# BSheetSchematicTemplateWWU.net
KiCad netlist of a schematic drawn in Altium Designer
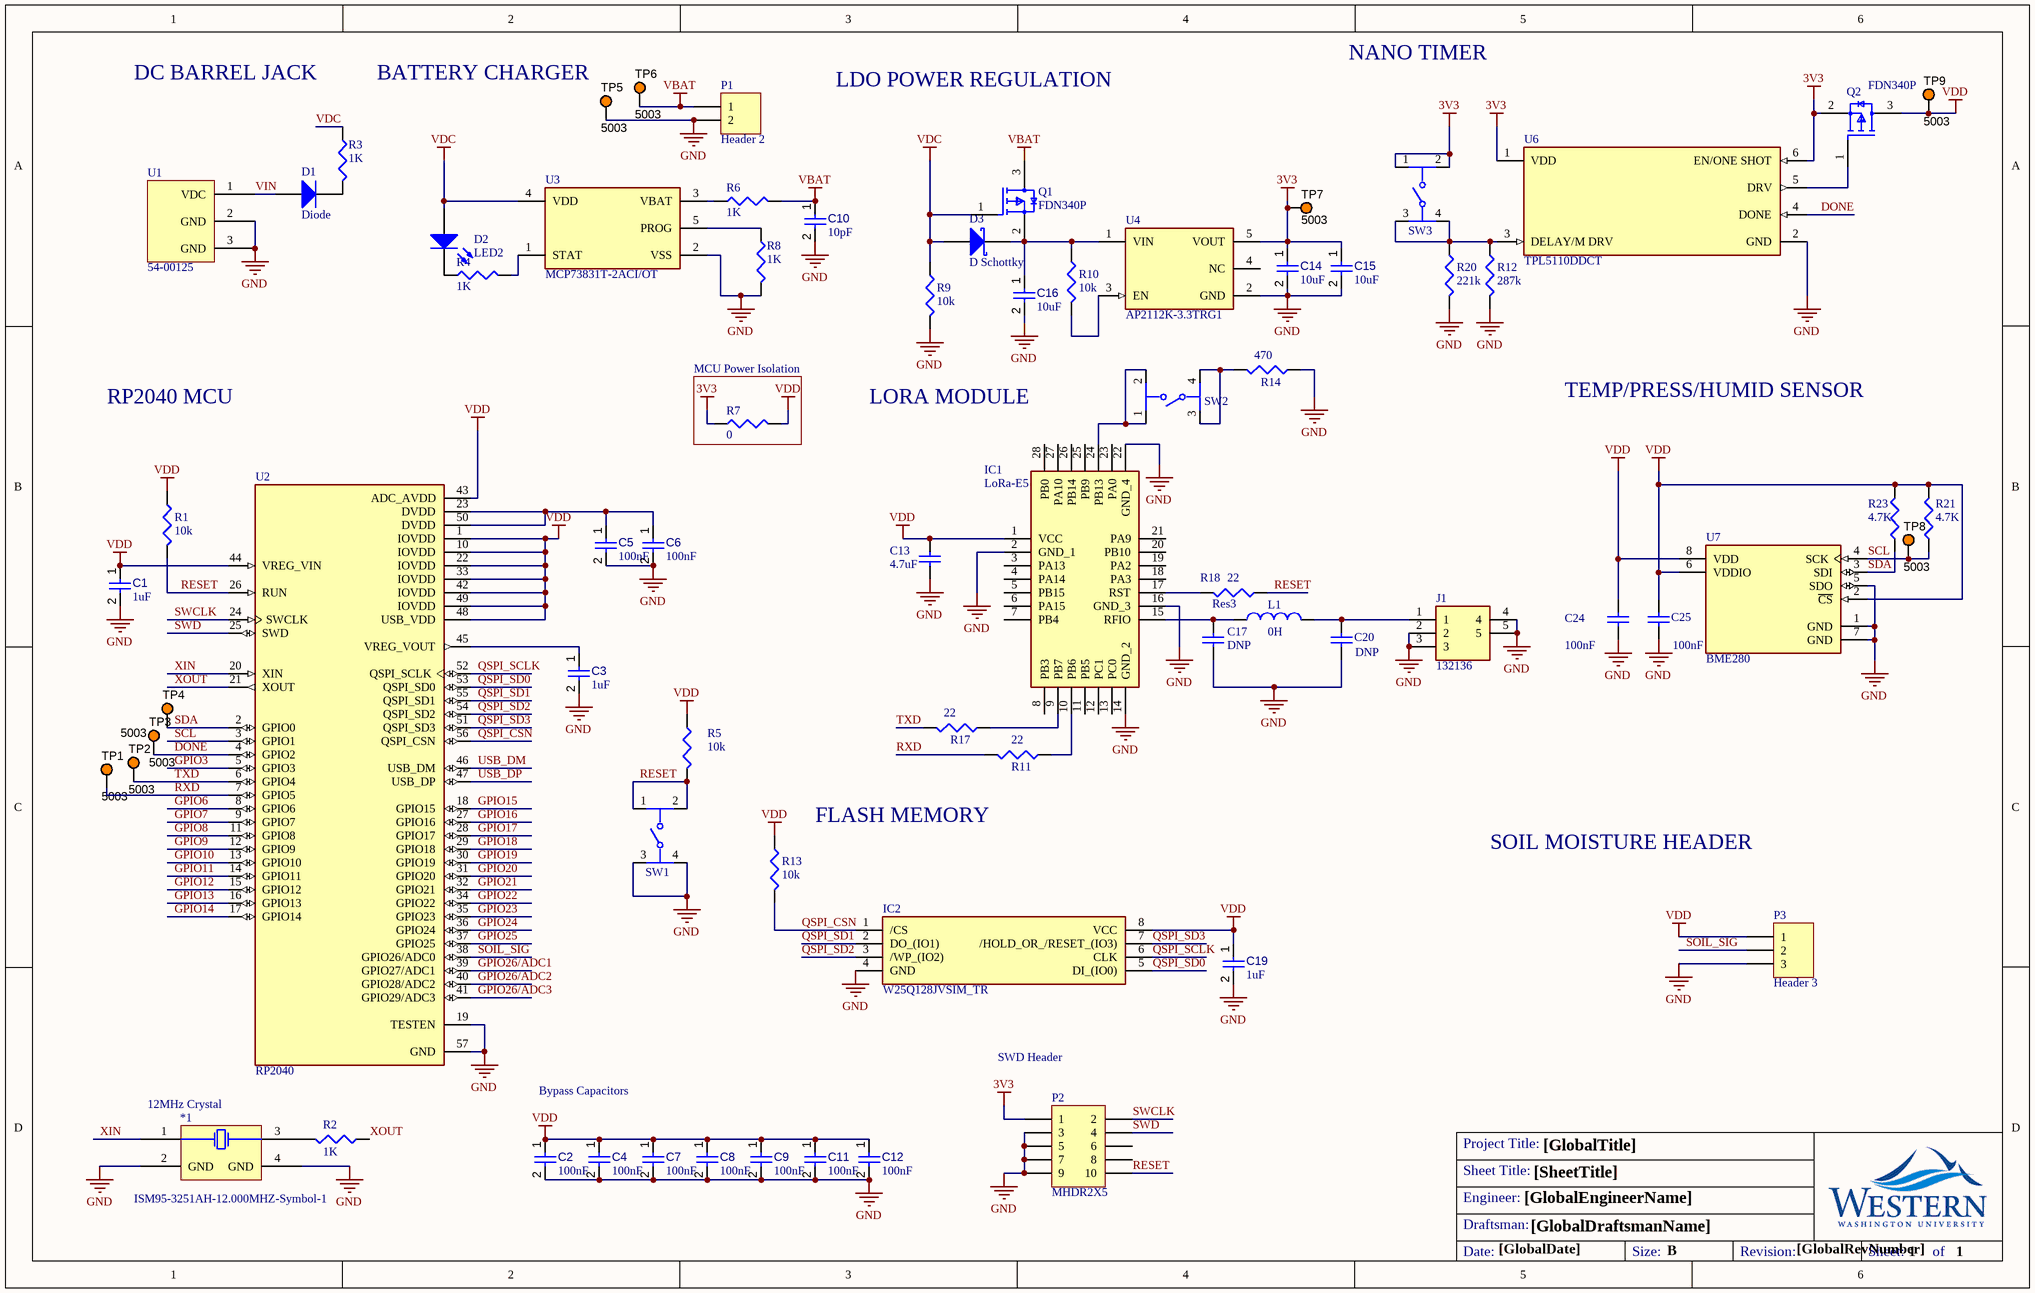
[diagram p0: BSheetSchematicTemplateWWU.SchDoc]

(export (version "E")
  (design (tool "Eeschema 10.0.6"))
  (components
    (comp (ref "*1")
      (value "ISM95-3251AH-12.000MHZ-Symbol-1")
      (footprint "OSC_ISM951251AH32000MHZ")
      (libsource (lib "SeniorProject") (part "ISM95-3251AH-12.000MHZ-Symbol-1"))
    )
    (comp (ref "C1")
      (value "1uF")
      (footprint "CAPC1608X87X35NL15T15")
      (description "Chip Capacitor, 10 pF, +/- 0.25 pF, 50 V, 0603 (1608 Metric)")
      (fields
        (field (name "TOLERANCE") "0.25%")
        (field (name "Comment") "Capacitor 10 pF +/- 0.25 pF 50 V 0603")
      )
      (libsource (lib "Western Washington University") (part "CAP-NP-2"))
    )
    (comp (ref "C2")
      (value "100nF")
      (footprint "CAPC1608X87X35NL15T15")
      (description "Chip Capacitor, 10 pF, +/- 0.25 pF, 50 V, 0603 (1608 Metric)")
      (fields
        (field (name "TOLERANCE") "0.25%")
        (field (name "Comment") "Capacitor 10 pF +/- 0.25 pF 50 V 0603")
      )
      (libsource (lib "Western Washington University") (part "CAP-NP-2"))
    )
    (comp (ref "C3")
      (value "1uF")
      (footprint "CAPC1608X87X35NL15T15")
      (description "Chip Capacitor, 10 pF, +/- 0.25 pF, 50 V, 0603 (1608 Metric)")
      (fields
        (field (name "TOLERANCE") "0.25%")
        (field (name "Comment") "Capacitor 10 pF +/- 0.25 pF 50 V 0603")
      )
      (libsource (lib "Western Washington University") (part "CAP-NP-2"))
    )
    (comp (ref "C4")
      (value "100nF")
      (footprint "CAPC1608X87X35NL15T15")
      (description "Chip Capacitor, 10 pF, +/- 0.25 pF, 50 V, 0603 (1608 Metric)")
      (fields
        (field (name "TOLERANCE") "0.25%")
        (field (name "Comment") "Capacitor 10 pF +/- 0.25 pF 50 V 0603")
      )
      (libsource (lib "Western Washington University") (part "CAP-NP-2"))
    )
    (comp (ref "C5")
      (value "100nF")
      (footprint "CAPC1608X87X35NL15T15")
      (description "Chip Capacitor, 10 pF, +/- 0.25 pF, 50 V, 0603 (1608 Metric)")
      (fields
        (field (name "TOLERANCE") "0.25%")
        (field (name "Comment") "Capacitor 10 pF +/- 0.25 pF 50 V 0603")
      )
      (libsource (lib "Western Washington University") (part "CAP-NP-2"))
    )
    (comp (ref "C6")
      (value "100nF")
      (footprint "CAPC1608X87X35NL15T15")
      (description "Chip Capacitor, 10 pF, +/- 0.25 pF, 50 V, 0603 (1608 Metric)")
      (fields
        (field (name "TOLERANCE") "0.25%")
        (field (name "Comment") "Capacitor 10 pF +/- 0.25 pF 50 V 0603")
      )
      (libsource (lib "Western Washington University") (part "CAP-NP-2"))
    )
    (comp (ref "C7")
      (value "100nF")
      (footprint "CAPC1608X87X35NL15T15")
      (description "Chip Capacitor, 10 pF, +/- 0.25 pF, 50 V, 0603 (1608 Metric)")
      (fields
        (field (name "TOLERANCE") "0.25%")
        (field (name "Comment") "Capacitor 10 pF +/- 0.25 pF 50 V 0603")
      )
      (libsource (lib "Western Washington University") (part "CAP-NP-2"))
    )
    (comp (ref "C8")
      (value "100nF")
      (footprint "CAPC1608X87X35NL15T15")
      (description "Chip Capacitor, 10 pF, +/- 0.25 pF, 50 V, 0603 (1608 Metric)")
      (fields
        (field (name "TOLERANCE") "0.25%")
        (field (name "Comment") "Capacitor 10 pF +/- 0.25 pF 50 V 0603")
      )
      (libsource (lib "Western Washington University") (part "CAP-NP-2"))
    )
    (comp (ref "C9")
      (value "100nF")
      (footprint "CAPC1608X87X35NL15T15")
      (description "Chip Capacitor, 10 pF, +/- 0.25 pF, 50 V, 0603 (1608 Metric)")
      (fields
        (field (name "TOLERANCE") "0.25%")
        (field (name "Comment") "Capacitor 10 pF +/- 0.25 pF 50 V 0603")
      )
      (libsource (lib "Western Washington University") (part "CAP-NP-2"))
    )
    (comp (ref "C10")
      (value "10pF")
      (footprint "CAPC1608X87X35NL15T15")
      (description "Chip Capacitor, 10 pF, +/- 0.25 pF, 50 V, 0603 (1608 Metric)")
      (fields
        (field (name "TOLERANCE") "0.25%")
        (field (name "Comment") "Capacitor 10 pF +/- 0.25 pF 50 V 0603")
      )
      (libsource (lib "Western Washington University") (part "CAP-NP-2"))
    )
    (comp (ref "C11")
      (value "100nF")
      (footprint "CAPC1608X87X35NL15T15")
      (description "Chip Capacitor, 10 pF, +/- 0.25 pF, 50 V, 0603 (1608 Metric)")
      (fields
        (field (name "TOLERANCE") "0.25%")
        (field (name "Comment") "Capacitor 10 pF +/- 0.25 pF 50 V 0603")
      )
      (libsource (lib "Western Washington University") (part "CAP-NP-2"))
    )
    (comp (ref "C12")
      (value "100nF")
      (footprint "CAPC1608X87X35NL15T15")
      (description "Chip Capacitor, 10 pF, +/- 0.25 pF, 50 V, 0603 (1608 Metric)")
      (fields
        (field (name "TOLERANCE") "0.25%")
        (field (name "Comment") "Capacitor 10 pF +/- 0.25 pF 50 V 0603")
      )
      (libsource (lib "Western Washington University") (part "CAP-NP-2"))
    )
    (comp (ref "C13")
      (value "4.7uF")
      (footprint "1608[0603]")
      (description "Capacitor (Semiconductor SIM Model)")
      (fields (field (name "Comment") "Cap Semi") (field (name "PUBLISHER") "Altium Limited"))
      (libsource (lib "Miscellaneous Devices") (part "Cap Semi"))
    )
    (comp (ref "C14")
      (value "10uF")
      (footprint "CAPC1608X87X35NL15T15")
      (description "Chip Capacitor, 10 pF, +/- 0.25 pF, 50 V, 0603 (1608 Metric)")
      (fields
        (field (name "TOLERANCE") "0.25%")
        (field (name "Comment") "Capacitor 10 pF +/- 0.25 pF 50 V 0603")
      )
      (libsource (lib "Western Washington University") (part "CAP-NP-2"))
    )
    (comp (ref "C15")
      (value "10uF")
      (footprint "CAPC1608X87X35NL15T15")
      (description "Chip Capacitor, 10 pF, +/- 0.25 pF, 50 V, 0603 (1608 Metric)")
      (fields
        (field (name "TOLERANCE") "0.25%")
        (field (name "Comment") "Capacitor 10 pF +/- 0.25 pF 50 V 0603")
      )
      (libsource (lib "Western Washington University") (part "CAP-NP-2"))
    )
    (comp (ref "C16")
      (value "10uF")
      (footprint "CAPC1608X87X35NL15T15")
      (description "Chip Capacitor, 10 pF, +/- 0.25 pF, 50 V, 0603 (1608 Metric)")
      (fields
        (field (name "TOLERANCE") "0.25%")
        (field (name "Comment") "Capacitor 10 pF +/- 0.25 pF 50 V 0603")
      )
      (libsource (lib "Western Washington University") (part "CAP-NP-2"))
    )
    (comp (ref "C17")
      (value "DNP")
      (footprint "1608[0603]")
      (description "Capacitor (Semiconductor SIM Model)")
      (fields (field (name "Comment") "Cap Semi") (field (name "PUBLISHER") "Altium Limited"))
      (libsource (lib "Miscellaneous Devices") (part "Cap Semi"))
    )
    (comp (ref "C19")
      (value "1uF")
      (footprint "CAPC1608X87X35NL15T15")
      (description "Chip Capacitor, 10 pF, +/- 0.25 pF, 50 V, 0603 (1608 Metric)")
      (fields
        (field (name "TOLERANCE") "0.25%")
        (field (name "Comment") "Capacitor 10 pF +/- 0.25 pF 50 V 0603")
      )
      (libsource (lib "Western Washington University") (part "CAP-NP-2"))
    )
    (comp (ref "C20")
      (value "DNP")
      (footprint "1608[0603]")
      (description "Capacitor (Semiconductor SIM Model)")
      (fields (field (name "Comment") "Cap Semi") (field (name "PUBLISHER") "Altium Limited"))
      (libsource (lib "Miscellaneous Devices") (part "Cap Semi"))
    )
    (comp (ref "C24")
      (value "100nF")
      (footprint "1608[0603]")
      (description "Capacitor (Semiconductor SIM Model)")
      (fields (field (name "Comment") "Cap Semi") (field (name "PUBLISHER") "Altium Limited"))
      (libsource (lib "Miscellaneous Devices") (part "Cap Semi"))
    )
    (comp (ref "C25")
      (value "100nF")
      (footprint "1608[0603]")
      (description "Capacitor (Semiconductor SIM Model)")
      (fields (field (name "Comment") "Cap Semi") (field (name "PUBLISHER") "Altium Limited"))
      (libsource (lib "Miscellaneous Devices") (part "Cap Semi"))
    )
    (comp (ref "D1")
      (value "Diode")
      (footprint "SMC")
      (description "Default Diode")
      (fields (field (name "PUBLISHER") "Altium Limited"))
      (libsource (lib "Miscellaneous Devices") (part "Diode"))
    )
    (comp (ref "D2")
      (value "LED2")
      (footprint "3.2X1.6X1.1")
      (description "Typical RED, GREEN, YELLOW, AMBER GaAs LED")
      (fields (field (name "PUBLISHER") "Altium Limited"))
      (libsource (lib "Miscellaneous Devices") (part "LED2"))
    )
    (comp (ref "D3")
      (value "D Schottky")
      (footprint "SMB")
      (description "Schottky Diode")
      (fields (field (name "PUBLISHER") "Altium Limited"))
      (libsource (lib "Miscellaneous Devices") (part "D Schottky"))
    )
    (comp (ref "IC1")
      (value "LoRa-E5")
      (footprint "SamacSys:LoRaE5")
      (description "Integrated Circuit")
      (libsource (lib "*") (part "LoRa-E5"))
    )
    (comp (ref "IC2")
      (value "W25Q128JVSIM_TR")
      (footprint "SOIC127P790X216-8N")
      (description "Integrated Circuit")
      (fields
        (field (name "MANUFACTURER_PART_NUMBER") "W25Q128JVSIM TR")
        (field (name "MOUSER PART NUMBER") "454-W25Q128JVSIMTR")
      )
      (libsource (lib "*") (part "W25Q128JVSIM_TR"))
    )
    (comp (ref "J1")
      (value "132136")
      (footprint "132136")
      (description "Connector")
      (fields (field (name "MOUSER PART NUMBER") "523-132136"))
      (libsource (lib "*") (part "132136"))
    )
    (comp (ref "L1")
      (value "0H")
      (footprint "0603")
      (description "Inductor")
      (fields (field (name "PUBLISHER") "Altium Limited"))
      (libsource (lib "Miscellaneous Devices") (part "Inductor"))
    )
    (comp (ref "P1")
      (value "Header 2")
      (footprint "HDR1X2")
      (description "Header, 2-Pin")
      (fields (field (name "PUBLISHER") "Altium Limited"))
      (libsource (lib "Miscellaneous Connectors") (part "Header 2"))
    )
    (comp (ref "P2")
      (value "MHDR2X5")
      (footprint "MHDR2X5")
      (description "Header, 5-Pin, Dual row")
      (fields (field (name "PUBLISHER") "Altium Limited"))
      (libsource (lib "Miscellaneous Connectors") (part "MHDR2X5"))
    )
    (comp (ref "P3")
      (value "Header 3")
      (footprint "HDR1X3")
      (description "Header, 3-Pin")
      (fields (field (name "PUBLISHER") "Altium Limited"))
      (libsource (lib "Miscellaneous Connectors") (part "Header 3"))
    )
    (comp (ref "Q1")
      (value "FDN340P")
      (footprint "FP-527AG-MFG")
      (description "MOSFET P-CH 20V 2A SSOT3")
      (libsource (lib "Altium Content Vault") (part "d23f43cc42f60b967b7caccf14518fd"))
    )
    (comp (ref "Q2")
      (value "FDN340P")
      (footprint "FP-527AG-MFG")
      (description "MOSFET P-CH 20V 2A SSOT3")
      (libsource (lib "Altium Content Vault") (part "d23f43cc42f60b967b7caccf14518fd"))
    )
    (comp (ref "R1")
      (value "10k")
      (footprint "J1-0603")
      (description "Resistor")
      (fields (field (name "Comment") "Res3") (field (name "PUBLISHER") "Altium Limited"))
      (libsource (lib "Miscellaneous Devices") (part "Res3"))
    )
    (comp (ref "R2")
      (value "1K")
      (footprint "J1-0603")
      (description "Resistor")
      (fields (field (name "Comment") "Res3") (field (name "PUBLISHER") "Altium Limited"))
      (libsource (lib "Miscellaneous Devices") (part "Res3"))
    )
    (comp (ref "R3")
      (value "1K")
      (footprint "J1-0603")
      (description "Resistor")
      (fields (field (name "Comment") "Res3") (field (name "PUBLISHER") "Altium Limited"))
      (libsource (lib "Miscellaneous Devices") (part "Res3"))
    )
    (comp (ref "R4")
      (value "1K")
      (footprint "J1-0603")
      (description "Resistor")
      (fields (field (name "Comment") "Res3") (field (name "PUBLISHER") "Altium Limited"))
      (libsource (lib "Miscellaneous Devices") (part "Res3"))
    )
    (comp (ref "R5")
      (value "10k")
      (footprint "J1-0603")
      (description "Resistor")
      (fields (field (name "Comment") "Res3") (field (name "PUBLISHER") "Altium Limited"))
      (libsource (lib "Miscellaneous Devices") (part "Res3"))
    )
    (comp (ref "R6")
      (value "1K")
      (footprint "J1-0603")
      (description "Resistor")
      (fields (field (name "Comment") "Res3") (field (name "PUBLISHER") "Altium Limited"))
      (libsource (lib "Miscellaneous Devices") (part "Res3"))
    )
    (comp (ref "R7")
      (value "0")
      (footprint "J1-0603")
      (description "Resistor")
      (fields (field (name "Comment") "Res3") (field (name "PUBLISHER") "Altium Limited"))
      (libsource (lib "Miscellaneous Devices") (part "Res3"))
    )
    (comp (ref "R8")
      (value "1K")
      (footprint "J1-0603")
      (description "Resistor")
      (fields (field (name "Comment") "Res3") (field (name "PUBLISHER") "Altium Limited"))
      (libsource (lib "Miscellaneous Devices") (part "Res3"))
    )
    (comp (ref "R9")
      (value "10k")
      (footprint "J1-0603")
      (description "Resistor")
      (fields (field (name "Comment") "Res3") (field (name "PUBLISHER") "Altium Limited"))
      (libsource (lib "Miscellaneous Devices") (part "Res3"))
    )
    (comp (ref "R10")
      (value "10k")
      (footprint "J1-0603")
      (description "Resistor")
      (fields (field (name "Comment") "Res3") (field (name "PUBLISHER") "Altium Limited"))
      (libsource (lib "Miscellaneous Devices") (part "Res3"))
    )
    (comp (ref "R11")
      (value "22")
      (footprint "J1-0603")
      (description "Resistor")
      (fields (field (name "Comment") "Res3") (field (name "PUBLISHER") "Altium Limited"))
      (libsource (lib "Miscellaneous Devices") (part "Res3"))
    )
    (comp (ref "R12")
      (value "287k")
      (footprint "J1-0603")
      (description "Resistor")
      (fields (field (name "Comment") "Res3") (field (name "PUBLISHER") "Altium Limited"))
      (libsource (lib "Miscellaneous Devices") (part "Res3"))
    )
    (comp (ref "R13")
      (value "10k")
      (footprint "J1-0603")
      (description "Resistor")
      (fields (field (name "Comment") "Res3") (field (name "PUBLISHER") "Altium Limited"))
      (libsource (lib "Miscellaneous Devices") (part "Res3"))
    )
    (comp (ref "R14")
      (value "470")
      (footprint "J1-0603")
      (description "Resistor")
      (fields (field (name "Comment") "Res3") (field (name "PUBLISHER") "Altium Limited"))
      (libsource (lib "Miscellaneous Devices") (part "Res3"))
    )
    (comp (ref "R17")
      (value "22")
      (footprint "J1-0603")
      (description "Resistor")
      (fields (field (name "Comment") "Res3") (field (name "PUBLISHER") "Altium Limited"))
      (libsource (lib "Miscellaneous Devices") (part "Res3"))
    )
    (comp (ref "R18")
      (value "Res3")
      (footprint "J1-0603")
      (description "Resistor")
      (fields (field (name "ALTIUM_VALUE") "22") (field (name "PUBLISHER") "Altium Limited"))
      (libsource (lib "Miscellaneous Devices") (part "Res3"))
    )
    (comp (ref "R20")
      (value "221k")
      (footprint "J1-0603")
      (description "Resistor")
      (fields (field (name "Comment") "Res3") (field (name "PUBLISHER") "Altium Limited"))
      (libsource (lib "Miscellaneous Devices") (part "Res3"))
    )
    (comp (ref "R21")
      (value "4.7K")
      (footprint "J1-0603")
      (description "Resistor")
      (fields (field (name "Comment") "Res3") (field (name "PUBLISHER") "Altium Limited"))
      (libsource (lib "Miscellaneous Devices") (part "Res3"))
    )
    (comp (ref "R23")
      (value "4.7K")
      (footprint "J1-0603")
      (description "Resistor")
      (fields (field (name "Comment") "Res3") (field (name "PUBLISHER") "Altium Limited"))
      (libsource (lib "Miscellaneous Devices") (part "Res3"))
    )
    (comp (ref "SW1")
      (value "PTS645SM43SMTR92LFS")
      (footprint "FP-PTS645SM43SMTR92LFS-MFG")
      (description "SWITCH TACTILE SPST-NO 0.05A 12V")
      (libsource (lib "Altium Content Vault") (part "1adf0dd01260c80cf25a44bfd6b99ba"))
    )
    (comp (ref "SW2")
      (value "PTS645SM43SMTR92LFS")
      (footprint "FP-PTS645SM43SMTR92LFS-MFG")
      (description "SWITCH TACTILE SPST-NO 0.05A 12V")
      (libsource (lib "Altium Content Vault") (part "1adf0dd01260c80cf25a44bfd6b99ba"))
    )
    (comp (ref "SW3")
      (value "PTS645SM43SMTR92LFS")
      (footprint "FP-PTS645SM43SMTR92LFS-MFG")
      (description "SWITCH TACTILE SPST-NO 0.05A 12V")
      (libsource (lib "Altium Content Vault") (part "1adf0dd01260c80cf25a44bfd6b99ba"))
    )
    (comp (ref "TP1")
      (value "5003")
      (footprint "KSTN-5003")
      (description "Test Point, Orange, Height 4.6 mm, Tail Length 3 mm, 1-Pin THD, RoHS")
      (fields (field (name "MANUFACTURER") "Keystone"))
      (libsource (lib "Western Washington University") (part "TESTPOINT_ORANGE"))
    )
    (comp (ref "TP2")
      (value "5003")
      (footprint "KSTN-5003")
      (description "Test Point, Orange, Height 4.6 mm, Tail Length 3 mm, 1-Pin THD, RoHS")
      (fields (field (name "MANUFACTURER") "Keystone"))
      (libsource (lib "Western Washington University") (part "TESTPOINT_ORANGE"))
    )
    (comp (ref "TP3")
      (value "5003")
      (footprint "KSTN-5003")
      (description "Test Point, Orange, Height 4.6 mm, Tail Length 3 mm, 1-Pin THD, RoHS")
      (fields (field (name "MANUFACTURER") "Keystone"))
      (libsource (lib "Western Washington University") (part "TESTPOINT_ORANGE"))
    )
    (comp (ref "TP4")
      (value "5003")
      (footprint "KSTN-5003")
      (description "Test Point, Orange, Height 4.6 mm, Tail Length 3 mm, 1-Pin THD, RoHS")
      (fields (field (name "MANUFACTURER") "Keystone"))
      (libsource (lib "Western Washington University") (part "TESTPOINT_ORANGE"))
    )
    (comp (ref "TP5")
      (value "5003")
      (footprint "KSTN-5003")
      (description "Test Point, Orange, Height 4.6 mm, Tail Length 3 mm, 1-Pin THD, RoHS")
      (fields (field (name "MANUFACTURER") "Keystone"))
      (libsource (lib "Western Washington University") (part "TESTPOINT_ORANGE"))
    )
    (comp (ref "TP6")
      (value "5003")
      (footprint "KSTN-5003")
      (description "Test Point, Orange, Height 4.6 mm, Tail Length 3 mm, 1-Pin THD, RoHS")
      (fields (field (name "MANUFACTURER") "Keystone"))
      (libsource (lib "Western Washington University") (part "TESTPOINT_ORANGE"))
    )
    (comp (ref "TP7")
      (value "5003")
      (footprint "KSTN-5003")
      (description "Test Point, Orange, Height 4.6 mm, Tail Length 3 mm, 1-Pin THD, RoHS")
      (fields (field (name "MANUFACTURER") "Keystone"))
      (libsource (lib "Western Washington University") (part "TESTPOINT_ORANGE"))
    )
    (comp (ref "TP8")
      (value "5003")
      (footprint "KSTN-5003")
      (description "Test Point, Orange, Height 4.6 mm, Tail Length 3 mm, 1-Pin THD, RoHS")
      (fields (field (name "MANUFACTURER") "Keystone"))
      (libsource (lib "Western Washington University") (part "TESTPOINT_ORANGE"))
    )
    (comp (ref "TP9")
      (value "5003")
      (footprint "KSTN-5003")
      (description "Test Point, Orange, Height 4.6 mm, Tail Length 3 mm, 1-Pin THD, RoHS")
      (fields (field (name "MANUFACTURER") "Keystone"))
      (libsource (lib "Western Washington University") (part "TESTPOINT_ORANGE"))
    )
    (comp (ref "U1")
      (value "54-00125")
      (footprint "54-00125")
      (description "3.5x1.1mm Barrel Jack Connector")
      (libsource (lib "SeniorProject") (part "54-00125"))
    )
    (comp (ref "U2")
      (value "RP2040")
      (footprint "QFN40P700X700X90-57N-D")
      (description "RP2040 Raspberry Pi Pico - ARMÂ® CortexÂ®-M0+ MCU 32-Bit Embedded Evaluation Board")
      (fields (field (name "MF") "Raspberry Pi"))
      (libsource (lib "RP2040") (part "RP2040"))
    )
    (comp (ref "U3")
      (value "MCP73831T-2ACI/OT")
      (footprint "FP-C04-091-OT-IPC_B")
      (description "IC CONTROLLR LI-ION 4.2V SOT23-5")
      (libsource (lib "Altium Content Vault") (part "61f5a3bb3429d9e0caadea342aa3b19"))
    )
    (comp (ref "U4")
      (value "AP2112K-3.3TRG1")
      (footprint "FP-SOT25-IPC_A")
      (description "IC REG LINEAR 3.3V 600MA SOT25")
      (libsource (lib "Altium Content Vault") (part "c8ab751aee5229183125ab046a11caa"))
    )
    (comp (ref "U6")
      (value "TPL5110DDCT")
      (footprint "FP-DDC0006A-MFG")
      (description "IC OSC PROG TIMER TSOT23-6")
      (fields
        (field (name "OCTOPART") "https://octopart.com/tpl5110ddct-texas+instruments-52670271")
        (field (name "MANUFACTURER") "Texas Instruments")
      )
      (libsource (lib "Altium Content Vault") (part "6ed543a5282c23458c04814cca5b1ac"))
    )
    (comp (ref "U7")
      (value "BME280")
      (footprint "FP-BME280-MFG")
      (description "SENSOR PRESSURE HUMIDITY TEMP")
      (libsource (lib "Altium Content Vault") (part "d58e2f6669bc67e6a2bc6a28610ca79"))
    )
  )
  (nets
    (net (code "1") (name "/DONE") (class "Default")
      (node (ref "TP3") (pin "1") (pinfunction "1_1") (pintype "passive"))
      (node (ref "U2") (pin "4") (pinfunction "GPIO2_4") (pintype "bidirectional"))
      (node (ref "U6") (pin "4") (pinfunction "DONE_4") (pintype "input"))
    )
    (net (code "2") (name "/GPIO3") (class "Default")
      (node (ref "U2") (pin "5") (pinfunction "GPIO3_5") (pintype "bidirectional"))
    )
    (net (code "3") (name "/GPIO6") (class "Default")
      (node (ref "U2") (pin "8") (pinfunction "GPIO6_8") (pintype "bidirectional"))
    )
    (net (code "4") (name "/GPIO7") (class "Default")
      (node (ref "U2") (pin "9") (pinfunction "GPIO7_9") (pintype "bidirectional"))
    )
    (net (code "5") (name "/GPIO8") (class "Default")
      (node (ref "U2") (pin "11") (pinfunction "GPIO8_11") (pintype "bidirectional"))
    )
    (net (code "6") (name "/GPIO9") (class "Default")
      (node (ref "U2") (pin "12") (pinfunction "GPIO9_12") (pintype "bidirectional"))
    )
    (net (code "7") (name "/GPIO10") (class "Default")
      (node (ref "U2") (pin "13") (pinfunction "GPIO10_13") (pintype "bidirectional"))
    )
    (net (code "8") (name "/GPIO11") (class "Default")
      (node (ref "U2") (pin "14") (pinfunction "GPIO11_14") (pintype "bidirectional"))
    )
    (net (code "9") (name "/GPIO12") (class "Default")
      (node (ref "U2") (pin "15") (pinfunction "GPIO12_15") (pintype "bidirectional"))
    )
    (net (code "10") (name "/GPIO13") (class "Default")
      (node (ref "U2") (pin "16") (pinfunction "GPIO13_16") (pintype "bidirectional"))
    )
    (net (code "11") (name "/GPIO14") (class "Default")
      (node (ref "U2") (pin "17") (pinfunction "GPIO14_17") (pintype "bidirectional"))
    )
    (net (code "12") (name "/GPIO15") (class "Default")
      (node (ref "U2") (pin "18") (pinfunction "GPIO15_18") (pintype "bidirectional"))
    )
    (net (code "13") (name "/GPIO16") (class "Default")
      (node (ref "U2") (pin "27") (pinfunction "GPIO16_27") (pintype "bidirectional"))
    )
    (net (code "14") (name "/GPIO17") (class "Default")
      (node (ref "U2") (pin "28") (pinfunction "GPIO17_28") (pintype "bidirectional"))
    )
    (net (code "15") (name "/GPIO18") (class "Default")
      (node (ref "U2") (pin "29") (pinfunction "GPIO18_29") (pintype "bidirectional"))
    )
    (net (code "16") (name "/GPIO19") (class "Default")
      (node (ref "U2") (pin "30") (pinfunction "GPIO19_30") (pintype "bidirectional"))
    )
    (net (code "17") (name "/GPIO20") (class "Default")
      (node (ref "U2") (pin "31") (pinfunction "GPIO20_31") (pintype "bidirectional"))
    )
    (net (code "18") (name "/GPIO21") (class "Default")
      (node (ref "U2") (pin "32") (pinfunction "GPIO21_32") (pintype "bidirectional"))
    )
    (net (code "19") (name "/GPIO22") (class "Default")
      (node (ref "U2") (pin "34") (pinfunction "GPIO22_34") (pintype "bidirectional"))
    )
    (net (code "20") (name "/GPIO23") (class "Default")
      (node (ref "U2") (pin "35") (pinfunction "GPIO23_35") (pintype "bidirectional"))
    )
    (net (code "21") (name "/GPIO24") (class "Default")
      (node (ref "U2") (pin "36") (pinfunction "GPIO24_36") (pintype "bidirectional"))
    )
    (net (code "22") (name "/GPIO25") (class "Default")
      (node (ref "U2") (pin "37") (pinfunction "GPIO25_37") (pintype "bidirectional"))
    )
    (net (code "23") (name "/GPIO26{slash}ADC1") (class "Default")
      (node (ref "U2") (pin "39") (pinfunction "GPIO27/ADC1_39") (pintype "bidirectional"))
    )
    (net (code "24") (name "/GPIO26{slash}ADC2") (class "Default")
      (node (ref "U2") (pin "40") (pinfunction "GPIO28/ADC2_40") (pintype "bidirectional"))
    )
    (net (code "25") (name "/GPIO26{slash}ADC3") (class "Default")
      (node (ref "U2") (pin "41") (pinfunction "GPIO29/ADC3_41") (pintype "bidirectional"))
    )
    (net (code "26") (name "/QSPI_CSN") (class "Default")
      (node (ref "IC2") (pin "1") (pinfunction "/CS_1") (pintype "passive"))
      (node (ref "R13") (pin "2") (pinfunction "2_2") (pintype "passive"))
      (node (ref "U2") (pin "56") (pinfunction "QSPI_CSN_56") (pintype "bidirectional"))
    )
    (net (code "27") (name "/QSPI_SCLK") (class "Default")
      (node (ref "IC2") (pin "6") (pinfunction "CLK_6") (pintype "passive"))
      (node (ref "U2") (pin "52") (pinfunction "QSPI_SCLK_52") (pintype "bidirectional"))
    )
    (net (code "28") (name "/QSPI_SD0") (class "Default")
      (node (ref "IC2") (pin "5") (pinfunction "DI_(IO0)_5") (pintype "passive"))
      (node (ref "U2") (pin "53") (pinfunction "QSPI_SD0_53") (pintype "bidirectional"))
    )
    (net (code "29") (name "/QSPI_SD1") (class "Default")
      (node (ref "IC2") (pin "2") (pinfunction "DO_(IO1)_2") (pintype "passive"))
      (node (ref "U2") (pin "55") (pinfunction "QSPI_SD1_55") (pintype "bidirectional"))
    )
    (net (code "30") (name "/QSPI_SD2") (class "Default")
      (node (ref "IC2") (pin "3") (pinfunction "/WP_(IO2)_3") (pintype "passive"))
      (node (ref "U2") (pin "54") (pinfunction "QSPI_SD2_54") (pintype "bidirectional"))
    )
    (net (code "31") (name "/QSPI_SD3") (class "Default")
      (node (ref "IC2") (pin "7") (pinfunction "/HOLD_OR_/RESET_(IO3)_7") (pintype "passive"))
      (node (ref "U2") (pin "51") (pinfunction "QSPI_SD3_51") (pintype "bidirectional"))
    )
    (net (code "32") (name "/RESET") (class "Default")
      (node (ref "P2") (pin "10") (pinfunction "10_10") (pintype "passive"))
      (node (ref "R1") (pin "2") (pinfunction "2_2") (pintype "passive"))
      (node (ref "R18") (pin "1") (pinfunction "1_1") (pintype "passive"))
      (node (ref "R5") (pin "2") (pinfunction "2_2") (pintype "passive"))
      (node (ref "SW1") (pin "1") (pinfunction "1_1") (pintype "passive"))
      (node (ref "SW1") (pin "2") (pinfunction "2_2") (pintype "passive"))
      (node (ref "U2") (pin "26") (pinfunction "RUN_26") (pintype "input"))
    )
    (net (code "33") (name "/RXD") (class "Default")
      (node (ref "R11") (pin "2") (pinfunction "2_2") (pintype "passive"))
      (node (ref "TP1") (pin "1") (pinfunction "1_1") (pintype "passive"))
      (node (ref "U2") (pin "7") (pinfunction "GPIO5_7") (pintype "bidirectional"))
    )
    (net (code "34") (name "/SCL") (class "Default")
      (node (ref "R21") (pin "1") (pinfunction "1_1") (pintype "passive"))
      (node (ref "TP8") (pin "1") (pinfunction "1_1") (pintype "passive"))
      (node (ref "U2") (pin "3") (pinfunction "GPIO1_3") (pintype "bidirectional"))
      (node (ref "U7") (pin "4") (pinfunction "SCK_4") (pintype "input"))
    )
    (net (code "35") (name "/SDA") (class "Default")
      (node (ref "R23") (pin "1") (pinfunction "1_1") (pintype "passive"))
      (node (ref "TP4") (pin "1") (pinfunction "1_1") (pintype "passive"))
      (node (ref "U2") (pin "2") (pinfunction "GPIO0_2") (pintype "bidirectional"))
      (node (ref "U7") (pin "3") (pinfunction "SDI_3") (pintype "bidirectional"))
    )
    (net (code "36") (name "/SOIL_SIG") (class "Default")
      (node (ref "P3") (pin "2") (pinfunction "2_2") (pintype "passive"))
      (node (ref "U2") (pin "38") (pinfunction "GPIO26/ADC0_38") (pintype "bidirectional"))
    )
    (net (code "37") (name "/SWCLK") (class "Default")
      (node (ref "P2") (pin "2") (pinfunction "2_2") (pintype "passive"))
      (node (ref "U2") (pin "24") (pinfunction "SWCLK_24") (pintype "input"))
    )
    (net (code "38") (name "/SWD") (class "Default")
      (node (ref "P2") (pin "4") (pinfunction "4_4") (pintype "passive"))
      (node (ref "U2") (pin "25") (pinfunction "SWD_25") (pintype "bidirectional"))
    )
    (net (code "39") (name "/TXD") (class "Default")
      (node (ref "R17") (pin "2") (pinfunction "2_2") (pintype "passive"))
      (node (ref "TP2") (pin "1") (pinfunction "1_1") (pintype "passive"))
      (node (ref "U2") (pin "6") (pinfunction "GPIO4_6") (pintype "bidirectional"))
    )
    (net (code "40") (name "/USB_DM") (class "Default")
      (node (ref "U2") (pin "46") (pinfunction "USB_DM_46") (pintype "bidirectional"))
    )
    (net (code "41") (name "/USB_DP") (class "Default")
      (node (ref "U2") (pin "47") (pinfunction "USB_DP_47") (pintype "bidirectional"))
    )
    (net (code "42") (name "/VIN") (class "Default")
      (node (ref "D1") (pin "1") (pinfunction "A_1") (pintype "passive"))
      (node (ref "U1") (pin "1") (pinfunction "VDC_1") (pintype "passive"))
    )
    (net (code "43") (name "/XIN") (class "Default")
      (node (ref "*1") (pin "1") (pinfunction "X1_1") (pintype "passive"))
      (node (ref "U2") (pin "20") (pinfunction "XIN_20") (pintype "input"))
    )
    (net (code "44") (name "/XOUT") (class "Default")
      (node (ref "R2") (pin "1") (pinfunction "1_1") (pintype "passive"))
      (node (ref "U2") (pin "21") (pinfunction "XOUT_21") (pintype "output"))
    )
    (net (code "45") (name "3V3") (class "Default")
      (node (ref "C14") (pin "1") (pinfunction "1_1") (pintype "passive"))
      (node (ref "C15") (pin "1") (pinfunction "1_1") (pintype "passive"))
      (node (ref "P2") (pin "1") (pinfunction "1_1") (pintype "passive"))
      (node (ref "Q2") (pin "2") (pinfunction "S_2") (pintype "passive"))
      (node (ref "R7") (pin "1") (pinfunction "1_1") (pintype "passive"))
      (node (ref "SW3") (pin "1") (pinfunction "1_1") (pintype "passive"))
      (node (ref "SW3") (pin "2") (pinfunction "2_2") (pintype "passive"))
      (node (ref "TP7") (pin "1") (pinfunction "1_1") (pintype "passive"))
      (node (ref "U4") (pin "5") (pinfunction "VOUT_5") (pintype "power_in"))
      (node (ref "U6") (pin "1") (pinfunction "VDD_1") (pintype "power_in"))
      (node (ref "U6") (pin "6") (pinfunction "EN/ONE_SHOT_6") (pintype "input"))
    )
    (net (code "46") (name "GND") (class "Default")
      (node (ref "*1") (pin "2") (pinfunction "GND_2") (pintype "power_in"))
      (node (ref "*1") (pin "4") (pinfunction "GND_4") (pintype "passive"))
      (node (ref "C1") (pin "2") (pinfunction "2_2") (pintype "passive"))
      (node (ref "C10") (pin "2") (pinfunction "2_2") (pintype "passive"))
      (node (ref "C11") (pin "2") (pinfunction "2_2") (pintype "passive"))
      (node (ref "C12") (pin "2") (pinfunction "2_2") (pintype "passive"))
      (node (ref "C13") (pin "1") (pinfunction "1_1") (pintype "passive"))
      (node (ref "C14") (pin "2") (pinfunction "2_2") (pintype "passive"))
      (node (ref "C15") (pin "2") (pinfunction "2_2") (pintype "passive"))
      (node (ref "C16") (pin "2") (pinfunction "2_2") (pintype "passive"))
      (node (ref "C17") (pin "1") (pinfunction "1_1") (pintype "passive"))
      (node (ref "C19") (pin "2") (pinfunction "2_2") (pintype "passive"))
      (node (ref "C2") (pin "2") (pinfunction "2_2") (pintype "passive"))
      (node (ref "C20") (pin "1") (pinfunction "1_1") (pintype "passive"))
      (node (ref "C24") (pin "1") (pinfunction "1_1") (pintype "passive"))
      (node (ref "C25") (pin "1") (pinfunction "1_1") (pintype "passive"))
      (node (ref "C3") (pin "2") (pinfunction "2_2") (pintype "passive"))
      (node (ref "C4") (pin "2") (pinfunction "2_2") (pintype "passive"))
      (node (ref "C5") (pin "2") (pinfunction "2_2") (pintype "passive"))
      (node (ref "C6") (pin "2") (pinfunction "2_2") (pintype "passive"))
      (node (ref "C7") (pin "2") (pinfunction "2_2") (pintype "passive"))
      (node (ref "C8") (pin "2") (pinfunction "2_2") (pintype "passive"))
      (node (ref "C9") (pin "2") (pinfunction "2_2") (pintype "passive"))
      (node (ref "IC1") (pin "14") (pinfunction "GND_2_14") (pintype "passive"))
      (node (ref "IC1") (pin "16") (pinfunction "GND_3_16") (pintype "passive"))
      (node (ref "IC1") (pin "2") (pinfunction "GND_1_2") (pintype "passive"))
      (node (ref "IC1") (pin "22") (pinfunction "GND_4_22") (pintype "passive"))
      (node (ref "IC2") (pin "4") (pinfunction "GND_4") (pintype "passive"))
      (node (ref "J1") (pin "2") (pinfunction "2_2") (pintype "passive"))
      (node (ref "J1") (pin "3") (pinfunction "3_3") (pintype "passive"))
      (node (ref "J1") (pin "4") (pinfunction "4_4") (pintype "passive"))
      (node (ref "J1") (pin "5") (pinfunction "5_5") (pintype "passive"))
      (node (ref "P1") (pin "2") (pinfunction "2_2") (pintype "passive"))
      (node (ref "P2") (pin "3") (pinfunction "3_3") (pintype "passive"))
      (node (ref "P2") (pin "5") (pinfunction "5_5") (pintype "passive"))
      (node (ref "P2") (pin "7") (pinfunction "7_7") (pintype "passive"))
      (node (ref "P2") (pin "9") (pinfunction "9_9") (pintype "passive"))
      (node (ref "P3") (pin "3") (pinfunction "3_3") (pintype "passive"))
      (node (ref "R12") (pin "2") (pinfunction "2_2") (pintype "passive"))
      (node (ref "R14") (pin "1") (pinfunction "1_1") (pintype "passive"))
      (node (ref "R20") (pin "2") (pinfunction "2_2") (pintype "passive"))
      (node (ref "R8") (pin "2") (pinfunction "2_2") (pintype "passive"))
      (node (ref "R9") (pin "2") (pinfunction "2_2") (pintype "passive"))
      (node (ref "SW1") (pin "3") (pinfunction "3_3") (pintype "passive"))
      (node (ref "SW1") (pin "4") (pinfunction "4_4") (pintype "passive"))
      (node (ref "TP5") (pin "1") (pinfunction "1_1") (pintype "passive"))
      (node (ref "U1") (pin "2") (pinfunction "GND_2") (pintype "passive"))
      (node (ref "U1") (pin "3") (pinfunction "GND_3") (pintype "passive"))
      (node (ref "U2") (pin "19") (pinfunction "TESTEN_19") (pintype "passive"))
      (node (ref "U2") (pin "57") (pinfunction "GND_57") (pintype "power_in"))
      (node (ref "U3") (pin "2") (pinfunction "VSS_2") (pintype "power_in"))
      (node (ref "U4") (pin "2") (pinfunction "GND_2") (pintype "power_in"))
      (node (ref "U6") (pin "2") (pinfunction "GND_2") (pintype "power_in"))
      (node (ref "U7") (pin "1") (pinfunction "GND_1") (pintype "power_in"))
      (node (ref "U7") (pin "5") (pinfunction "SDO_5") (pintype "bidirectional"))
      (node (ref "U7") (pin "7") (pinfunction "GND_7") (pintype "power_in"))
    )
    (net (code "47") (name "Net-(*1-X2)") (class "Default")
      (node (ref "*1") (pin "3") (pinfunction "X2_3") (pintype "passive"))
      (node (ref "R2") (pin "2") (pinfunction "2_2") (pintype "passive"))
    )
    (net (code "48") (name "Net-(C5-Pad1)") (class "Default")
      (node (ref "C5") (pin "1") (pinfunction "1_1") (pintype "passive"))
      (node (ref "C6") (pin "1") (pinfunction "1_1") (pintype "passive"))
      (node (ref "U2") (pin "23") (pinfunction "DVDD_23") (pintype "power_in"))
      (node (ref "U2") (pin "50") (pinfunction "DVDD_50") (pintype "power_in"))
    )
    (net (code "49") (name "Net-(C20-Pad2)") (class "Default")
      (node (ref "C20") (pin "2") (pinfunction "2_2") (pintype "passive"))
      (node (ref "J1") (pin "1") (pinfunction "1_1") (pintype "passive"))
      (node (ref "L1") (pin "2") (pinfunction "2_2") (pintype "passive"))
    )
    (net (code "50") (name "Net-(D1-K)") (class "Default")
      (node (ref "D1") (pin "2") (pinfunction "K_2") (pintype "passive"))
      (node (ref "R3") (pin "2") (pinfunction "2_2") (pintype "passive"))
    )
    (net (code "51") (name "Net-(D2-K)") (class "Default")
      (node (ref "D2") (pin "2") (pinfunction "K_2") (pintype "passive"))
      (node (ref "R4") (pin "1") (pinfunction "1_1") (pintype "passive"))
    )
    (net (code "52") (name "Net-(D3-K)") (class "Default")
      (node (ref "C16") (pin "1") (pinfunction "1_1") (pintype "passive"))
      (node (ref "D3") (pin "2") (pinfunction "K_2") (pintype "passive"))
      (node (ref "Q1") (pin "2") (pinfunction "S_2") (pintype "passive"))
      (node (ref "R10") (pin "1") (pinfunction "1_1") (pintype "passive"))
      (node (ref "U4") (pin "1") (pinfunction "VIN_1") (pintype "power_in"))
    )
    (net (code "53") (name "Net-(IC1-PB6)") (class "Default")
      (node (ref "IC1") (pin "10") (pinfunction "PB6_10") (pintype "passive"))
      (node (ref "R11") (pin "1") (pinfunction "1_1") (pintype "passive"))
    )
    (net (code "54") (name "Net-(IC1-PB7)") (class "Default")
      (node (ref "IC1") (pin "9") (pinfunction "PB7_9") (pintype "passive"))
      (node (ref "R17") (pin "1") (pinfunction "1_1") (pintype "passive"))
    )
    (net (code "55") (name "Net-(IC1-PB13)") (class "Default")
      (node (ref "IC1") (pin "24") (pinfunction "PB13_24") (pintype "passive"))
      (node (ref "SW2") (pin "1") (pinfunction "1_1") (pintype "passive"))
      (node (ref "SW2") (pin "2") (pinfunction "2_2") (pintype "passive"))
    )
    (net (code "56") (name "Net-(IC1-RFIO)") (class "Default")
      (node (ref "C17") (pin "2") (pinfunction "2_2") (pintype "passive"))
      (node (ref "IC1") (pin "15") (pinfunction "RFIO_15") (pintype "passive"))
      (node (ref "L1") (pin "1") (pinfunction "1_1") (pintype "passive"))
    )
    (net (code "57") (name "Net-(IC1-RST)") (class "Default")
      (node (ref "IC1") (pin "17") (pinfunction "RST_17") (pintype "passive"))
      (node (ref "R18") (pin "2") (pinfunction "2_2") (pintype "passive"))
    )
    (net (code "58") (name "Net-(Q2-G)") (class "Default")
      (node (ref "Q2") (pin "1") (pinfunction "G_1") (pintype "passive"))
      (node (ref "U6") (pin "5") (pinfunction "DRV_5") (pintype "output"))
    )
    (net (code "59") (name "Net-(R14-Pad2)") (class "Default")
      (node (ref "R14") (pin "2") (pinfunction "2_2") (pintype "passive"))
      (node (ref "SW2") (pin "3") (pinfunction "3_3") (pintype "passive"))
      (node (ref "SW2") (pin "4") (pinfunction "4_4") (pintype "passive"))
    )
    (net (code "60") (name "Net-(U2-VREG_VOUT)") (class "Default")
      (node (ref "C3") (pin "1") (pinfunction "1_1") (pintype "passive"))
      (node (ref "U2") (pin "45") (pinfunction "VREG_VOUT_45") (pintype "output"))
    )
    (net (code "61") (name "Net-(U3-PROG)") (class "Default")
      (node (ref "R8") (pin "1") (pinfunction "1_1") (pintype "passive"))
      (node (ref "U3") (pin "5") (pinfunction "PROG_5") (pintype "passive"))
    )
    (net (code "62") (name "Net-(U3-STAT)") (class "Default")
      (node (ref "R4") (pin "2") (pinfunction "2_2") (pintype "passive"))
      (node (ref "U3") (pin "1") (pinfunction "STAT_1") (pintype "passive"))
    )
    (net (code "63") (name "Net-(U3-VBAT)") (class "Default")
      (node (ref "R6") (pin "1") (pinfunction "1_1") (pintype "passive"))
      (node (ref "U3") (pin "3") (pinfunction "VBAT_3") (pintype "power_in"))
    )
    (net (code "64") (name "Net-(U4-EN)") (class "Default")
      (node (ref "R10") (pin "2") (pinfunction "2_2") (pintype "passive"))
      (node (ref "U4") (pin "3") (pinfunction "EN_3") (pintype "input"))
    )
    (net (code "65") (name "Net-(U6-DELAY{slash}M_DRV)") (class "Default")
      (node (ref "R12") (pin "1") (pinfunction "1_1") (pintype "passive"))
      (node (ref "R20") (pin "1") (pinfunction "1_1") (pintype "passive"))
      (node (ref "SW3") (pin "3") (pinfunction "3_3") (pintype "passive"))
      (node (ref "SW3") (pin "4") (pinfunction "4_4") (pintype "passive"))
      (node (ref "U6") (pin "3") (pinfunction "DELAY/M_DRV_3") (pintype "input"))
    )
    (net (code "66") (name "VBAT") (class "Default")
      (node (ref "C10") (pin "1") (pinfunction "1_1") (pintype "passive"))
      (node (ref "P1") (pin "1") (pinfunction "1_1") (pintype "passive"))
      (node (ref "Q1") (pin "3") (pinfunction "D_3") (pintype "passive"))
      (node (ref "R6") (pin "2") (pinfunction "2_2") (pintype "passive"))
      (node (ref "TP6") (pin "1") (pinfunction "1_1") (pintype "passive"))
    )
    (net (code "67") (name "VDC") (class "Default")
      (node (ref "D2") (pin "1") (pinfunction "A_1") (pintype "passive"))
      (node (ref "D3") (pin "1") (pinfunction "A_1") (pintype "passive"))
      (node (ref "Q1") (pin "1") (pinfunction "G_1") (pintype "passive"))
      (node (ref "R3") (pin "1") (pinfunction "1_1") (pintype "passive"))
      (node (ref "R9") (pin "1") (pinfunction "1_1") (pintype "passive"))
      (node (ref "U3") (pin "4") (pinfunction "VDD_4") (pintype "power_in"))
    )
    (net (code "68") (name "VDD") (class "Default")
      (node (ref "C1") (pin "1") (pinfunction "1_1") (pintype "passive"))
      (node (ref "C11") (pin "1") (pinfunction "1_1") (pintype "passive"))
      (node (ref "C12") (pin "1") (pinfunction "1_1") (pintype "passive"))
      (node (ref "C13") (pin "2") (pinfunction "2_2") (pintype "passive"))
      (node (ref "C19") (pin "1") (pinfunction "1_1") (pintype "passive"))
      (node (ref "C2") (pin "1") (pinfunction "1_1") (pintype "passive"))
      (node (ref "C24") (pin "2") (pinfunction "2_2") (pintype "passive"))
      (node (ref "C25") (pin "2") (pinfunction "2_2") (pintype "passive"))
      (node (ref "C4") (pin "1") (pinfunction "1_1") (pintype "passive"))
      (node (ref "C7") (pin "1") (pinfunction "1_1") (pintype "passive"))
      (node (ref "C8") (pin "1") (pinfunction "1_1") (pintype "passive"))
      (node (ref "C9") (pin "1") (pinfunction "1_1") (pintype "passive"))
      (node (ref "IC1") (pin "1") (pinfunction "VCC_1") (pintype "passive"))
      (node (ref "IC2") (pin "8") (pinfunction "VCC_8") (pintype "passive"))
      (node (ref "P3") (pin "1") (pinfunction "1_1") (pintype "passive"))
      (node (ref "Q2") (pin "3") (pinfunction "D_3") (pintype "passive"))
      (node (ref "R1") (pin "1") (pinfunction "1_1") (pintype "passive"))
      (node (ref "R13") (pin "1") (pinfunction "1_1") (pintype "passive"))
      (node (ref "R21") (pin "2") (pinfunction "2_2") (pintype "passive"))
      (node (ref "R23") (pin "2") (pinfunction "2_2") (pintype "passive"))
      (node (ref "R5") (pin "1") (pinfunction "1_1") (pintype "passive"))
      (node (ref "R7") (pin "2") (pinfunction "2_2") (pintype "passive"))
      (node (ref "TP9") (pin "1") (pinfunction "1_1") (pintype "passive"))
      (node (ref "U2") (pin "1") (pinfunction "IOVDD_1") (pintype "power_in"))
      (node (ref "U2") (pin "10") (pinfunction "IOVDD_10") (pintype "power_in"))
      (node (ref "U2") (pin "22") (pinfunction "IOVDD_22") (pintype "power_in"))
      (node (ref "U2") (pin "33") (pinfunction "IOVDD_33") (pintype "power_in"))
      (node (ref "U2") (pin "42") (pinfunction "IOVDD_42") (pintype "power_in"))
      (node (ref "U2") (pin "43") (pinfunction "ADC_AVDD_43") (pintype "power_in"))
      (node (ref "U2") (pin "44") (pinfunction "VREG_VIN_44") (pintype "input"))
      (node (ref "U2") (pin "48") (pinfunction "USB_VDD_48") (pintype "power_in"))
      (node (ref "U2") (pin "49") (pinfunction "IOVDD_49") (pintype "power_in"))
      (node (ref "U7") (pin "2") (pinfunction "~{CS}_2") (pintype "input"))
      (node (ref "U7") (pin "6") (pinfunction "VDDIO_6") (pintype "power_in"))
      (node (ref "U7") (pin "8") (pinfunction "VDD_8") (pintype "power_in"))
    )
    (net (code "69") (name "unconnected-(IC1-PA0-Pad23)") (class "Default")
      (node (ref "IC1") (pin "23") (pinfunction "PA0_23") (pintype "passive"))
    )
    (net (code "70") (name "unconnected-(IC1-PA2-Pad19)") (class "Default")
      (node (ref "IC1") (pin "19") (pinfunction "PA2_19") (pintype "passive"))
    )
    (net (code "71") (name "unconnected-(IC1-PA3-Pad18)") (class "Default")
      (node (ref "IC1") (pin "18") (pinfunction "PA3_18") (pintype "passive"))
    )
    (net (code "72") (name "unconnected-(IC1-PA9-Pad21)") (class "Default")
      (node (ref "IC1") (pin "21") (pinfunction "PA9_21") (pintype "passive"))
    )
    (net (code "73") (name "unconnected-(IC1-PA10-Pad27)") (class "Default")
      (node (ref "IC1") (pin "27") (pinfunction "PA10_27") (pintype "passive"))
    )
    (net (code "74") (name "unconnected-(IC1-PA13-Pad3)") (class "Default")
      (node (ref "IC1") (pin "3") (pinfunction "PA13_3") (pintype "passive"))
    )
    (net (code "75") (name "unconnected-(IC1-PA14-Pad4)") (class "Default")
      (node (ref "IC1") (pin "4") (pinfunction "PA14_4") (pintype "passive"))
    )
    (net (code "76") (name "unconnected-(IC1-PA15-Pad6)") (class "Default")
      (node (ref "IC1") (pin "6") (pinfunction "PA15_6") (pintype "passive"))
    )
    (net (code "77") (name "unconnected-(IC1-PB0-Pad28)") (class "Default")
      (node (ref "IC1") (pin "28") (pinfunction "PB0_28") (pintype "passive"))
    )
    (net (code "78") (name "unconnected-(IC1-PB3-Pad8)") (class "Default")
      (node (ref "IC1") (pin "8") (pinfunction "PB3_8") (pintype "passive"))
    )
    (net (code "79") (name "unconnected-(IC1-PB4-Pad7)") (class "Default")
      (node (ref "IC1") (pin "7") (pinfunction "PB4_7") (pintype "passive"))
    )
    (net (code "80") (name "unconnected-(IC1-PB5-Pad11)") (class "Default")
      (node (ref "IC1") (pin "11") (pinfunction "PB5_11") (pintype "passive"))
    )
    (net (code "81") (name "unconnected-(IC1-PB9-Pad25)") (class "Default")
      (node (ref "IC1") (pin "25") (pinfunction "PB9_25") (pintype "passive"))
    )
    (net (code "82") (name "unconnected-(IC1-PB10-Pad20)") (class "Default")
      (node (ref "IC1") (pin "20") (pinfunction "PB10_20") (pintype "passive"))
    )
    (net (code "83") (name "unconnected-(IC1-PB14-Pad26)") (class "Default")
      (node (ref "IC1") (pin "26") (pinfunction "PB14_26") (pintype "passive"))
    )
    (net (code "84") (name "unconnected-(IC1-PB15-Pad5)") (class "Default")
      (node (ref "IC1") (pin "5") (pinfunction "PB15_5") (pintype "passive"))
    )
    (net (code "85") (name "unconnected-(IC1-PC0-Pad13)") (class "Default")
      (node (ref "IC1") (pin "13") (pinfunction "PC0_13") (pintype "passive"))
    )
    (net (code "86") (name "unconnected-(IC1-PC1-Pad12)") (class "Default")
      (node (ref "IC1") (pin "12") (pinfunction "PC1_12") (pintype "passive"))
    )
    (net (code "87") (name "unconnected-(P2-Pad6)") (class "Default")
      (node (ref "P2") (pin "6") (pinfunction "6_6") (pintype "passive"))
    )
    (net (code "88") (name "unconnected-(P2-Pad8)") (class "Default")
      (node (ref "P2") (pin "8") (pinfunction "8_8") (pintype "passive"))
    )
    (net (code "89") (name "unconnected-(U4-NC-Pad4)") (class "Default")
      (node (ref "U4") (pin "4") (pinfunction "NC_4") (pintype "passive"))
    )
  )
)
